# power-input.net
KiCad netlist of a schematic drawn in Altium Designer
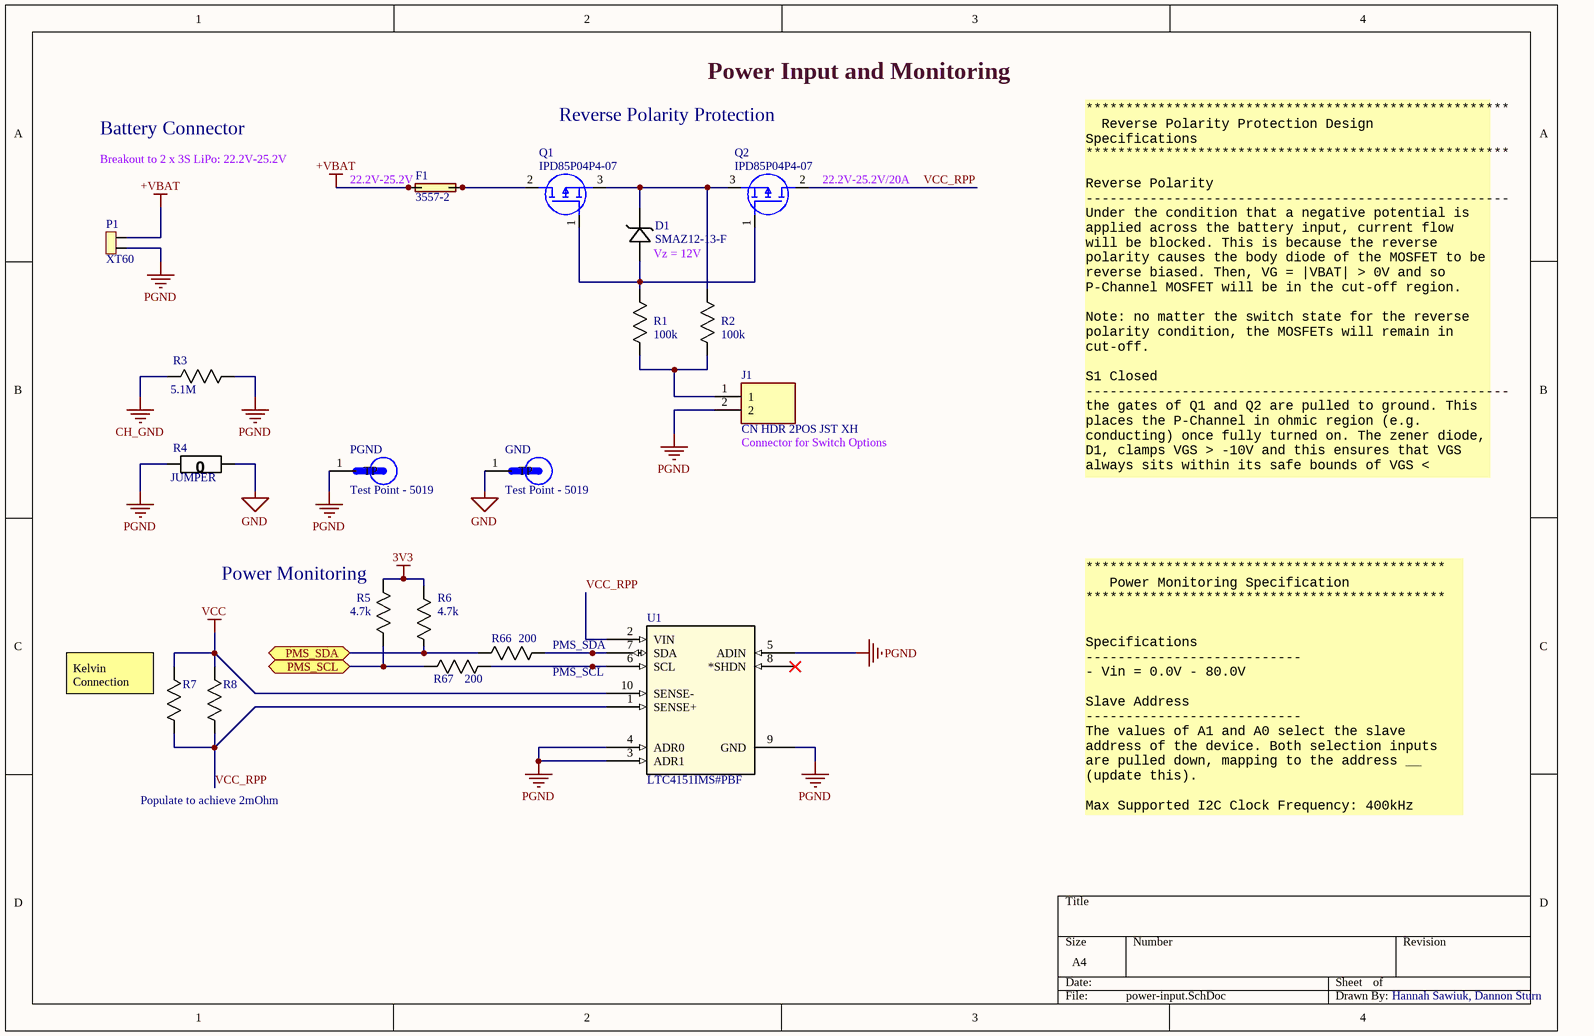
[diagram p0: power-input.SchDoc]

(export (version "E")
  (design (tool "Eeschema 10.0.6"))
  (components
    (comp (ref "D1")
      (value "SMAZ12-13-F")
      (footprint "SMA_DIO-L")
      (description "Zener Diode 12 V 1 W ±5% Surface Mount SMA")
      (fields
        (field (name "PART NUMBER") "DIODE ZENER 12V 1W")
        (field (name "COPYRIGHT") "Copyright (C) 2021 Ultra Librarian. All rights reserved.")
      )
      (libsource (lib "Diode_Library") (part "DIODE ZENER 12V 1W"))
    )
    (comp (ref "F1")
      (value "3557-2")
      (footprint "FUSE-3549-2")
      (description "Fuse Block 30A 500V 1 Circuit Blade Through Hole")
      (fields (field (name "MF") "Keystone Electronics") (field (name "PART NUMBER") "FUSE BLADE"))
      (libsource (lib "Fuse_Library") (part "FUSE BLADE"))
    )
    (comp (ref "GND")
      (value "Test Point - 5019")
      (footprint "TP380X203")
      (description "PC Test Point, Miniature Phosphor Bronze, Silver Plating Surface Mount Mounting Type")
      (fields (field (name "MP") "5019") (field (name "MF") "Keystone Electronics"))
      (libsource (lib "IC_Library") (part "Test Point - 5019"))
    )
    (comp (ref "J1")
      (value "CN HDR 2POS JST XH")
      (footprint "JST_S2B-XH-A(LF)(SN)")
      (description "Connector Header Through Hole 2 position 0.098 _2.50mm_\r\nJST XH")
      (fields (field (name "MP") "B2B-XH-A_LF__SN_") (field (name "MF") "JST Sales"))
      (libsource (lib "Connector_Library") (part "CN HDR 2POS JST XH"))
    )
    (comp (ref "P1")
      (value "XT60")
      (footprint "Amass_XT60PW-M")
      (description "XT60 CONNECTORS FEMALE PAIR")
      (fields (field (name "MF") "SparkFun Electronics") (field (name "MP") "PRT-10474"))
      (libsource (lib "Connector_Library") (part "XT60 Connector"))
    )
    (comp (ref "PGND")
      (value "Test Point - 5019")
      (footprint "TP380X203")
      (description "PC Test Point, Miniature Phosphor Bronze, Silver Plating Surface Mount Mounting Type")
      (fields (field (name "MP") "5019") (field (name "MF") "Keystone Electronics"))
      (libsource (lib "IC_Library") (part "Test Point - 5019"))
    )
    (comp (ref "PMS_SCL")
      (value "Test Point (Via)")
      (footprint "TP")
      (libsource (lib "IC_Library") (part "Test Point (Via)"))
    )
    (comp (ref "PMS_SDA")
      (value "Test Point (Via)")
      (footprint "TP")
      (libsource (lib "IC_Library") (part "Test Point (Via)"))
    )
    (comp (ref "Q1")
      (value "IPD85P04P4-07")
      (footprint "DPAK (TO-252)")
      (description "P-Channel 40 V 85A (Tc) 88W (Tc) Surface Mount PG-TO252-3-313")
      (fields (field (name "PART NUMBER") "MOSFET IPD85P04P4-07"))
      (libsource (lib "Transistor_Library") (part "MOSFET IPD85P04P4-07"))
    )
    (comp (ref "Q2")
      (value "IPD85P04P4-07")
      (footprint "DPAK (TO-252)")
      (description "P-Channel 40 V 85A (Tc) 88W (Tc) Surface Mount PG-TO252-3-313")
      (fields (field (name "PART NUMBER") "MOSFET IPD85P04P4-07"))
      (libsource (lib "Transistor_Library") (part "MOSFET IPD85P04P4-07"))
    )
    (comp (ref "R1")
      (value "100k")
      (footprint "0603")
      (description "RES SMD 100K OHM 1% 1/8W 0603")
      (fields (field (name "TOLERANCE") "1%") (field (name "PART NUMBER") "RES 100k 1/8W - 1%"))
      (libsource (lib "Resistor_Library") (part "RES 100k 1/8W 1%"))
    )
    (comp (ref "R2")
      (value "100k")
      (footprint "0603")
      (description "RES SMD 100K OHM 1% 1/8W 0603")
      (fields (field (name "TOLERANCE") "1%") (field (name "PART NUMBER") "RES 100k 1/8W - 1%"))
      (libsource (lib "Resistor_Library") (part "RES 100k 1/8W 1%"))
    )
    (comp (ref "R3")
      (value "5.1M")
      (footprint "0603")
      (description "RES SMD 5.1 MOHM 5% 1/8W 0603")
      (fields (field (name "TOLERANCE") "5%") (field (name "PART NUMBER") "RES 5.1M 1/8W-5%"))
      (libsource (lib "Resistor_Library") (part "RES 5.1M 1/8W-5%"))
    )
    (comp (ref "R4")
      (value "JUMPER")
      (footprint "1210")
      (description "RES SMD 0 OHM JUMPER GENERIC 0603")
      (fields (field (name "PART NUMBER") "RES 0 JUMPER"))
      (libsource (lib "Resistor_Library") (part "RES 0 JUMPER"))
    )
    (comp (ref "R5")
      (value "4.7k")
      (footprint "0603")
      (description "RES SMD 4.7k OHM 5% 1/8W 0603")
      (fields (field (name "TOLERANCE") "5%") (field (name "PART NUMBER") "RES 4.7k 1/8W - 5%"))
      (libsource (lib "") (part "RES 4.7k 1/8W - 5%_1"))
    )
    (comp (ref "R6")
      (value "4.7k")
      (footprint "0603")
      (description "RES SMD 4.7k OHM 5% 1/8W 0603")
      (fields (field (name "TOLERANCE") "5%") (field (name "PART NUMBER") "RES 4.7k 1/8W - 5%"))
      (libsource (lib "Resistor_Library") (part "RES 4.7k 1/8W - 5%"))
    )
    (comp (ref "R7")
      (value "2mOHM")
      (footprint "2512")
      (description "RES SMD 2m OHM 1% 1W 2512")
      (fields (field (name "TOLERANCE") "1%") (field (name "PART NUMBER") "RES 2m 1W"))
      (libsource (lib "Resistor_Library") (part "RES 2m 1W"))
    )
    (comp (ref "R8")
      (value "2mOHM")
      (footprint "2512")
      (description "RES SMD 2m OHM 1% 1W 2512")
      (fields (field (name "TOLERANCE") "1%") (field (name "PART NUMBER") "RES 2m 1W"))
      (libsource (lib "Resistor_Library") (part "RES 2m 1W"))
    )
    (comp (ref "R66")
      (value "200")
      (footprint "0603")
      (description "RES SMD 200 OHM 5% 1/8W 0603")
      (fields (field (name "TOLERANCE") "5%") (field (name "PART NUMBER") "RES 200.0 1/8W"))
      (libsource (lib "Resistor_Library") (part "RES 200.0 1/8W"))
    )
    (comp (ref "R67")
      (value "200")
      (footprint "0603")
      (description "RES SMD 200 OHM 5% 1/8W 0603")
      (fields (field (name "TOLERANCE") "5%") (field (name "PART NUMBER") "RES 200.0 1/8W"))
      (libsource (lib "Resistor_Library") (part "RES 200.0 1/8W"))
    )
    (comp (ref "U1")
      (value "LTC4151IMS#PBF")
      (footprint "MSOP-10_MS_LIT")
      (description "IC CURRENT MONITOR(12BIT) 10MSOP")
      (fields
        (field (name "MANUFACTURER_PART_NUMBER") "ltc4151ims#pbf")
        (field (name "COPYRIGHT") "Copyright (C) 2021 Ultra Librarian. All rights reserved.")
      )
      (libsource (lib "IC_Library") (part "ltc4151ims#pbf"))
    )
  )
  (nets
    (net (code "1") (name "+VBAT") (class "Default")
      (node (ref "F1") (pin "3") (pinfunction "2A_3") (pintype "passive"))
      (node (ref "F1") (pin "4") (pinfunction "2B_4") (pintype "passive"))
      (node (ref "P1") (pin "2") (pinfunction "2_2") (pintype "passive"))
    )
    (net (code "2") (name "/PMS_SCL") (class "Default")
      (node (ref "R5") (pin "1") (pinfunction "R1_1") (pintype "passive"))
      (node (ref "R67") (pin "2") (pinfunction "R2_2") (pintype "passive"))
    )
    (net (code "3") (name "/PMS_SDA") (class "Default")
      (node (ref "R6") (pin "1") (pinfunction "R1_1") (pintype "passive"))
      (node (ref "R66") (pin "2") (pinfunction "R2_2") (pintype "passive"))
    )
    (net (code "4") (name "/VCC_RPP") (class "Default")
      (node (ref "Q2") (pin "2") (pinfunction "D_2") (pintype "passive"))
      (node (ref "R7") (pin "2") (pinfunction "R2_2") (pintype "passive"))
      (node (ref "R8") (pin "2") (pinfunction "R2_2") (pintype "passive"))
      (node (ref "U1") (pin "1") (pinfunction "SENSE+_1") (pintype "input"))
      (node (ref "U1") (pin "2") (pinfunction "VIN_2") (pintype "input"))
    )
    (net (code "5") (name "3V3") (class "Default")
      (node (ref "R5") (pin "2") (pinfunction "R2_2") (pintype "passive"))
      (node (ref "R6") (pin "2") (pinfunction "R2_2") (pintype "passive"))
    )
    (net (code "6") (name "CH_GND") (class "Default")
      (node (ref "R3") (pin "2") (pinfunction "R2_2") (pintype "passive"))
    )
    (net (code "7") (name "GND") (class "Default")
      (node (ref "GND") (pin "1") (pinfunction "TP_1") (pintype "passive"))
      (node (ref "R4") (pin "1") (pinfunction "R1_1") (pintype "passive"))
    )
    (net (code "8") (name "Net-(F1-1A)") (class "Default")
      (node (ref "F1") (pin "1") (pinfunction "1A_1") (pintype "passive"))
      (node (ref "F1") (pin "2") (pinfunction "1B_2") (pintype "passive"))
      (node (ref "Q1") (pin "2") (pinfunction "D_2") (pintype "passive"))
    )
    (net (code "9") (name "Net-(Q1-G)") (class "Default")
      (node (ref "D1") (pin "2") (pinfunction "2_2") (pintype "passive"))
      (node (ref "Q1") (pin "1") (pinfunction "G_1") (pintype "passive"))
      (node (ref "Q2") (pin "1") (pinfunction "G_1") (pintype "passive"))
      (node (ref "R1") (pin "1") (pinfunction "R1_1") (pintype "passive"))
    )
    (net (code "10") (name "Net-(Q1-S)") (class "Default")
      (node (ref "D1") (pin "1") (pinfunction "1_1") (pintype "passive"))
      (node (ref "Q1") (pin "3") (pinfunction "S_3") (pintype "passive"))
      (node (ref "Q2") (pin "3") (pinfunction "S_3") (pintype "passive"))
      (node (ref "R2") (pin "1") (pinfunction "R1_1") (pintype "passive"))
    )
    (net (code "11") (name "Net-(R1-R2)") (class "Default")
      (node (ref "J1") (pin "1") (pinfunction "1_1") (pintype "passive"))
      (node (ref "R1") (pin "2") (pinfunction "R2_2") (pintype "passive"))
      (node (ref "R2") (pin "2") (pinfunction "R2_2") (pintype "passive"))
    )
    (net (code "12") (name "Net-(R66-R1)") (class "Default")
      (node (ref "PMS_SDA") (pin "1") (pinfunction "1_1") (pintype "passive"))
      (node (ref "R66") (pin "1") (pinfunction "R1_1") (pintype "passive"))
      (node (ref "U1") (pin "7") (pinfunction "SDA_7") (pintype "bidirectional"))
    )
    (net (code "13") (name "Net-(R67-R1)") (class "Default")
      (node (ref "PMS_SCL") (pin "1") (pinfunction "1_1") (pintype "passive"))
      (node (ref "R67") (pin "1") (pinfunction "R1_1") (pintype "passive"))
      (node (ref "U1") (pin "6") (pinfunction "SCL_6") (pintype "input"))
    )
    (net (code "14") (name "PGND") (class "Default")
      (node (ref "J1") (pin "2") (pinfunction "2_2") (pintype "passive"))
      (node (ref "P1") (pin "1") (pinfunction "1_1") (pintype "passive"))
      (node (ref "PGND") (pin "1") (pinfunction "TP_1") (pintype "passive"))
      (node (ref "R3") (pin "1") (pinfunction "R1_1") (pintype "passive"))
      (node (ref "R4") (pin "2") (pinfunction "R2_2") (pintype "passive"))
      (node (ref "U1") (pin "3") (pinfunction "ADR1_3") (pintype "input"))
      (node (ref "U1") (pin "4") (pinfunction "ADR0_4") (pintype "input"))
      (node (ref "U1") (pin "5") (pinfunction "ADIN_5") (pintype "input"))
      (node (ref "U1") (pin "9") (pinfunction "GND_9") (pintype "power_in"))
    )
    (net (code "15") (name "VCC") (class "Default")
      (node (ref "R7") (pin "1") (pinfunction "R1_1") (pintype "passive"))
      (node (ref "R8") (pin "1") (pinfunction "R1_1") (pintype "passive"))
      (node (ref "U1") (pin "10") (pinfunction "SENSE-_10") (pintype "input"))
    )
    (net (code "16") (name "unconnected-(U1-*SHDN-Pad8)") (class "Default")
      (node (ref "U1") (pin "8") (pinfunction "*SHDN_8") (pintype "input+no_connect"))
    )
  )
)
